# NANO_STM32F103_2.net
KiCad netlist of a schematic drawn in Altium Designer
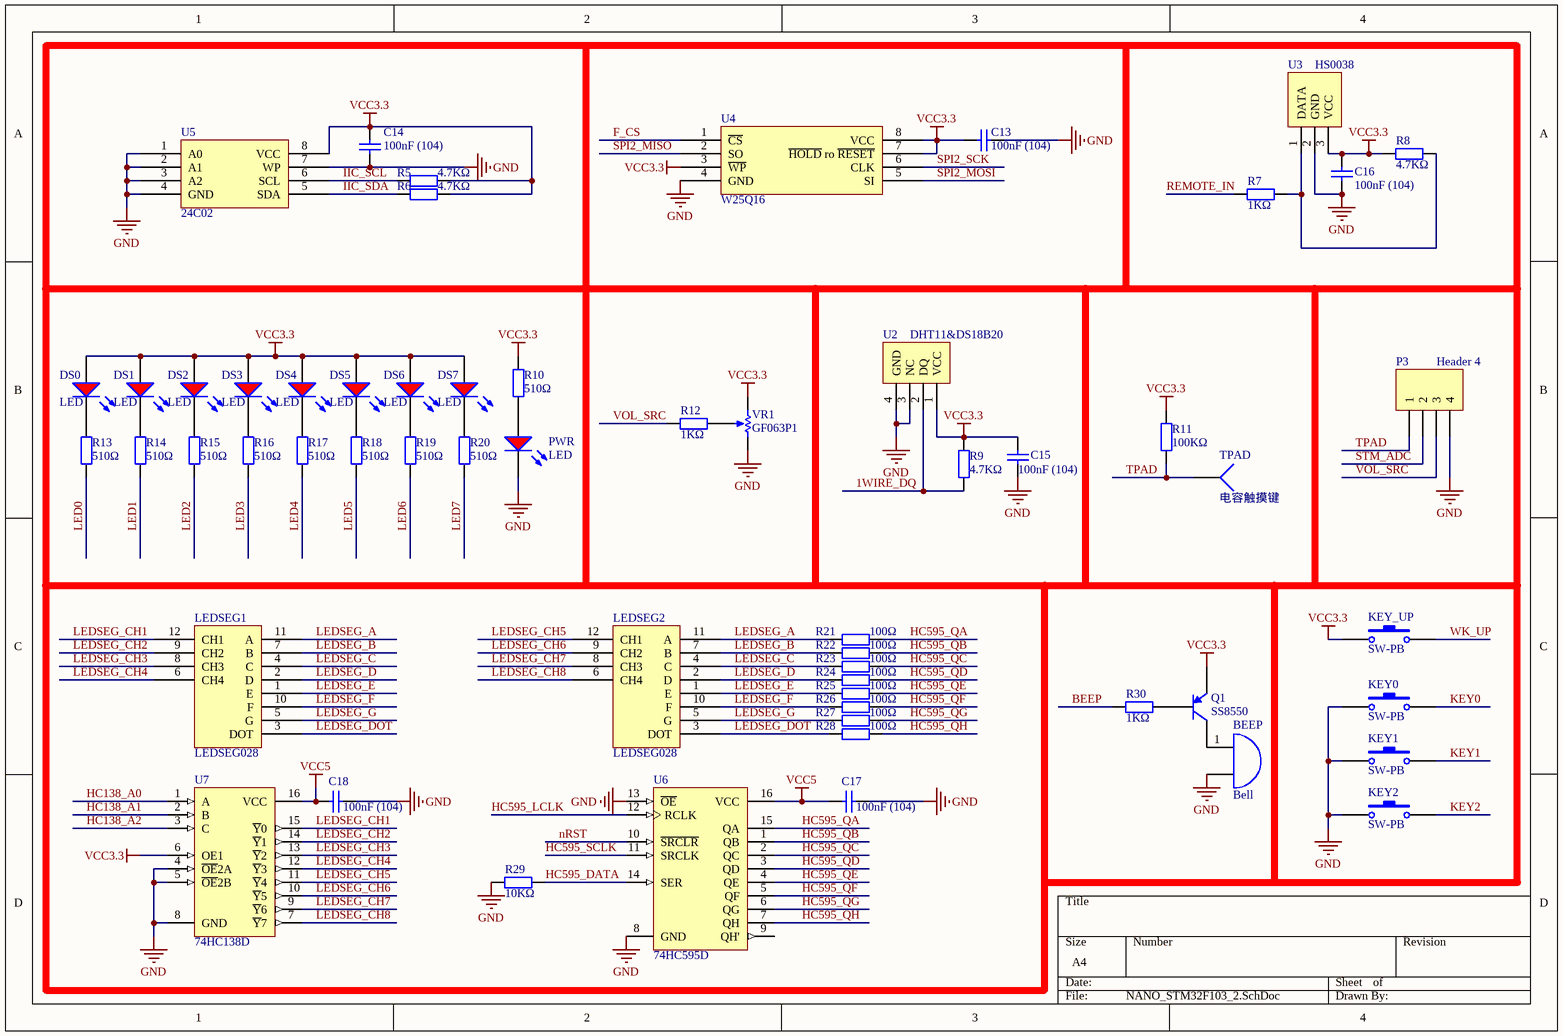
[diagram p0: NANO_STM32F103_2.SchDoc]

(export (version "E")
  (design (tool "Eeschema 10.0.6"))
  (components
    (comp (ref "BEEP")
      (value "Bell")
      (footprint "NANO_STM32F103:PIN2")
      (description "Electrical Bell")
      (fields (field (name "PUBLISHER") "Altium Limited"))
      (libsource (lib "Miscellaneous Devices") (part "Bell"))
    )
    (comp (ref "C13")
      (value "100nF (104)")
      (footprint "NANO_STM32F103:0603_C")
      (description "贴片电容")
      (libsource (lib "Miscellaneous Devices LC") (part "0603 100nF (104) 10% 50V"))
    )
    (comp (ref "C14")
      (value "100nF (104)")
      (footprint "NANO_STM32F103:0603_C")
      (description "贴片电容")
      (libsource (lib "Miscellaneous Devices LC") (part "0603 100nF (104) 10% 50V"))
    )
    (comp (ref "C15")
      (value "100nF (104)")
      (footprint "NANO_STM32F103:0603_C")
      (description "贴片电容")
      (libsource (lib "Miscellaneous Devices LC") (part "0603 100nF (104) 10% 50V"))
    )
    (comp (ref "C16")
      (value "100nF (104)")
      (footprint "NANO_STM32F103:0603_C")
      (description "贴片电容")
      (libsource (lib "Miscellaneous Devices LC") (part "0603 100nF (104) 10% 50V"))
    )
    (comp (ref "C17")
      (value "100nF (104)")
      (footprint "NANO_STM32F103:0603_C")
      (description "贴片电容")
      (libsource (lib "Miscellaneous Devices LC") (part "0603 100nF (104) 10% 50V"))
    )
    (comp (ref "C18")
      (value "100nF (104)")
      (footprint "NANO_STM32F103:0603_C")
      (description "贴片电容")
      (libsource (lib "Miscellaneous Devices LC") (part "0603 100nF (104) 10% 50V"))
    )
    (comp (ref "DS0")
      (value "LED")
      (footprint "NANO_STM32F103:0805_LED_S1")
      (description "发光二极管")
      (libsource (lib "Miscellaneous Devices LC") (part "0603 红灯"))
    )
    (comp (ref "DS1")
      (value "LED")
      (footprint "NANO_STM32F103:0805_LED_S1")
      (description "发光二极管")
      (libsource (lib "Miscellaneous Devices LC") (part "0603 红灯"))
    )
    (comp (ref "DS2")
      (value "LED")
      (footprint "NANO_STM32F103:0805_LED_S1")
      (description "发光二极管")
      (libsource (lib "Miscellaneous Devices LC") (part "0603 红灯"))
    )
    (comp (ref "DS3")
      (value "LED")
      (footprint "NANO_STM32F103:0805_LED_S1")
      (description "发光二极管")
      (libsource (lib "Miscellaneous Devices LC") (part "0603 红灯"))
    )
    (comp (ref "DS4")
      (value "LED")
      (footprint "NANO_STM32F103:0805_LED_S1")
      (description "发光二极管")
      (libsource (lib "Miscellaneous Devices LC") (part "0603 红灯"))
    )
    (comp (ref "DS5")
      (value "LED")
      (footprint "NANO_STM32F103:0805_LED_S1")
      (description "发光二极管")
      (libsource (lib "Miscellaneous Devices LC") (part "0603 红灯"))
    )
    (comp (ref "DS6")
      (value "LED")
      (footprint "NANO_STM32F103:0805_LED_S1")
      (description "发光二极管")
      (libsource (lib "Miscellaneous Devices LC") (part "0603 红灯"))
    )
    (comp (ref "DS7")
      (value "LED")
      (footprint "NANO_STM32F103:0805_LED_S1")
      (description "发光二极管")
      (libsource (lib "Miscellaneous Devices LC") (part "0603 红灯"))
    )
    (comp (ref "KEY0")
      (value "SW-PB")
      (footprint "NANO_STM32F103:SPST-2")
      (description "Switch")
      (fields (field (name "PUBLISHER") "Altium Limited"))
      (libsource (lib "Miscellaneous Devices") (part "SW-PB"))
    )
    (comp (ref "KEY1")
      (value "SW-PB")
      (footprint "NANO_STM32F103:SPST-2")
      (description "Switch")
      (fields (field (name "PUBLISHER") "Altium Limited"))
      (libsource (lib "Miscellaneous Devices") (part "SW-PB"))
    )
    (comp (ref "KEY2")
      (value "SW-PB")
      (footprint "NANO_STM32F103:SPST-2")
      (description "Switch")
      (fields (field (name "PUBLISHER") "Altium Limited"))
      (libsource (lib "Miscellaneous Devices") (part "SW-PB"))
    )
    (comp (ref "KEY_UP")
      (value "SW-PB")
      (footprint "NANO_STM32F103:SPST-2")
      (description "Switch")
      (fields (field (name "PUBLISHER") "Altium Limited"))
      (libsource (lib "Miscellaneous Devices") (part "SW-PB"))
    )
    (comp (ref "LEDSEG1")
      (value "LEDSEG028")
      (footprint "NANO_STM32F103:HDR1X12")
      (description "四位八段数码管_共阴极")
      (libsource (lib "NANO_STM32F103") (part "LEDSEG028"))
    )
    (comp (ref "LEDSEG2")
      (value "LEDSEG028")
      (footprint "NANO_STM32F103:HDR1X12")
      (description "四位八段数码管_共阴极")
      (libsource (lib "NANO_STM32F103") (part "LEDSEG028"))
    )
    (comp (ref "P3")
      (value "Header 4")
      (footprint "NANO_STM32F103:HDR1X4")
      (description "Header, 4-Pin")
      (fields (field (name "PUBLISHER") "Altium Limited"))
      (libsource (lib "Miscellaneous Connectors") (part "Header 4"))
    )
    (comp (ref "PWR")
      (value "LED")
      (footprint "NANO_STM32F103:0805_LED_S1")
      (description "发光二极管")
      (libsource (lib "Miscellaneous Devices LC") (part "0603 红灯"))
    )
    (comp (ref "Q1")
      (value "SS8550")
      (footprint "NANO_STM32F103:SOT-23(SOT-23-3)")
      (description "PNP三极管")
      (libsource (lib "Miscellaneous Devices LC") (part "SOT-23 SS8550 Y2"))
    )
    (comp (ref "R5")
      (value "4.7KΩ")
      (footprint "NANO_STM32F103:0603_R")
      (description "贴片电阻")
      (libsource (lib "Miscellaneous Devices LC") (part "0603 4.7KΩ (4701) 1%"))
    )
    (comp (ref "R6")
      (value "4.7KΩ")
      (footprint "NANO_STM32F103:0603_R")
      (description "贴片电阻")
      (libsource (lib "Miscellaneous Devices LC") (part "0603 4.7KΩ (4701) 1%"))
    )
    (comp (ref "R7")
      (value "1KΩ")
      (footprint "NANO_STM32F103:0603_R")
      (description "贴片电阻")
      (libsource (lib "Miscellaneous Devices LC") (part "0603 1KΩ (1001) 1%"))
    )
    (comp (ref "R8")
      (value "4.7KΩ")
      (footprint "NANO_STM32F103:0603_R")
      (description "贴片电阻")
      (libsource (lib "Miscellaneous Devices LC") (part "0603 4.7KΩ (4701) 1%"))
    )
    (comp (ref "R9")
      (value "4.7KΩ")
      (footprint "NANO_STM32F103:0603_R")
      (description "贴片电阻")
      (libsource (lib "") (part "0603 4.7KΩ (4701) 1%_1"))
    )
    (comp (ref "R10")
      (value "510Ω")
      (footprint "NANO_STM32F103:0603_R")
      (description "贴片电阻")
      (libsource (lib "Miscellaneous Devices LC") (part "0603 510Ω (5100) 1%"))
    )
    (comp (ref "R11")
      (value "100KΩ")
      (footprint "NANO_STM32F103:0603_R")
      (description "贴片电阻")
      (libsource (lib "Miscellaneous Devices LC") (part "0603 100KΩ (1003) 1%"))
    )
    (comp (ref "R12")
      (value "1KΩ")
      (footprint "NANO_STM32F103:0603_R")
      (description "贴片电阻")
      (libsource (lib "Miscellaneous Devices LC") (part "0603 1KΩ (1001) 1%"))
    )
    (comp (ref "R13")
      (value "510Ω")
      (footprint "NANO_STM32F103:0603_R")
      (description "贴片电阻")
      (libsource (lib "Miscellaneous Devices LC") (part "0603 510Ω (5100) 1%"))
    )
    (comp (ref "R14")
      (value "510Ω")
      (footprint "NANO_STM32F103:0603_R")
      (description "贴片电阻")
      (libsource (lib "Miscellaneous Devices LC") (part "0603 510Ω (5100) 1%"))
    )
    (comp (ref "R15")
      (value "510Ω")
      (footprint "NANO_STM32F103:0603_R")
      (description "贴片电阻")
      (libsource (lib "Miscellaneous Devices LC") (part "0603 510Ω (5100) 1%"))
    )
    (comp (ref "R16")
      (value "510Ω")
      (footprint "NANO_STM32F103:0603_R")
      (description "贴片电阻")
      (libsource (lib "Miscellaneous Devices LC") (part "0603 510Ω (5100) 1%"))
    )
    (comp (ref "R17")
      (value "510Ω")
      (footprint "NANO_STM32F103:0603_R")
      (description "贴片电阻")
      (libsource (lib "Miscellaneous Devices LC") (part "0603 510Ω (5100) 1%"))
    )
    (comp (ref "R18")
      (value "510Ω")
      (footprint "NANO_STM32F103:0603_R")
      (description "贴片电阻")
      (libsource (lib "Miscellaneous Devices LC") (part "0603 510Ω (5100) 1%"))
    )
    (comp (ref "R19")
      (value "510Ω")
      (footprint "NANO_STM32F103:0603_R")
      (description "贴片电阻")
      (libsource (lib "Miscellaneous Devices LC") (part "0603 510Ω (5100) 1%"))
    )
    (comp (ref "R20")
      (value "510Ω")
      (footprint "NANO_STM32F103:0603_R")
      (description "贴片电阻")
      (libsource (lib "Miscellaneous Devices LC") (part "0603 510Ω (5100) 1%"))
    )
    (comp (ref "R21")
      (value "100Ω")
      (footprint "NANO_STM32F103:0603_R")
      (description "贴片电阻")
      (libsource (lib "Miscellaneous Devices LC") (part "0603 100Ω (1000) 1%"))
    )
    (comp (ref "R22")
      (value "100Ω")
      (footprint "NANO_STM32F103:0603_R")
      (description "贴片电阻")
      (libsource (lib "Miscellaneous Devices LC") (part "0603 100Ω (1000) 1%"))
    )
    (comp (ref "R23")
      (value "100Ω")
      (footprint "NANO_STM32F103:0603_R")
      (description "贴片电阻")
      (libsource (lib "Miscellaneous Devices LC") (part "0603 100Ω (1000) 1%"))
    )
    (comp (ref "R24")
      (value "100Ω")
      (footprint "NANO_STM32F103:0603_R")
      (description "贴片电阻")
      (libsource (lib "Miscellaneous Devices LC") (part "0603 100Ω (1000) 1%"))
    )
    (comp (ref "R25")
      (value "100Ω")
      (footprint "NANO_STM32F103:0603_R")
      (description "贴片电阻")
      (libsource (lib "Miscellaneous Devices LC") (part "0603 100Ω (1000) 1%"))
    )
    (comp (ref "R26")
      (value "100Ω")
      (footprint "NANO_STM32F103:0603_R")
      (description "贴片电阻")
      (libsource (lib "Miscellaneous Devices LC") (part "0603 100Ω (1000) 1%"))
    )
    (comp (ref "R27")
      (value "100Ω")
      (footprint "NANO_STM32F103:0603_R")
      (description "贴片电阻")
      (libsource (lib "Miscellaneous Devices LC") (part "0603 100Ω (1000) 1%"))
    )
    (comp (ref "R28")
      (value "100Ω")
      (footprint "NANO_STM32F103:0603_R")
      (description "贴片电阻")
      (libsource (lib "Miscellaneous Devices LC") (part "0603 100Ω (1000) 1%"))
    )
    (comp (ref "R29")
      (value "10KΩ")
      (footprint "NANO_STM32F103:0603_R")
      (description "贴片电阻")
      (libsource (lib "Miscellaneous Devices LC") (part "0603 10KΩ (1002) 1%"))
    )
    (comp (ref "R30")
      (value "1KΩ")
      (footprint "NANO_STM32F103:0603_R")
      (description "贴片电阻")
      (libsource (lib "Miscellaneous Devices LC") (part "0603 1KΩ (1001) 1%"))
    )
    (comp (ref "TPAD")
      (value "电容触摸键")
      (footprint "NANO_STM32F103:TPAD")
      (fields (field (name "PUBLISHER") "Altium Limited"))
      (libsource (lib "Miscellaneous Connectors") (part "Socket"))
    )
    (comp (ref "U2")
      (value "DHT11&DS18B20")
      (footprint "DHT11&DS18B20")
      (description "DHT11或DS18B20_2.54mm")
      (libsource (lib "NANO_STM32F103_2") (part "DHT11&DS18B20"))
    )
    (comp (ref "U3")
      (value "HS0038")
      (footprint "NANO_STM32F103:HS0038")
      (description "HS0038_2.54mm")
      (libsource (lib "NANO_STM32F103_2") (part "HS0038"))
    )
    (comp (ref "U4")
      (value "W25Q16")
      (footprint "NANO_STM32F103:SOIC-8_208mil")
      (description "Flash ROM")
      (libsource (lib "Miscellaneous Devices LC") (part "W25Q128FVSIG_[C35101]"))
    )
    (comp (ref "U5")
      (value "24C02")
      (footprint "NANO_STM32F103:SOIC-8_150mil")
      (libsource (lib "Miscellaneous Devices LC") (part "CAN/TJA1050T/CM_[C6952]"))
    )
    (comp (ref "U6")
      (value "74HC595D")
      (footprint "NANO_STM32F103:SOIC-16_150mil")
      (description "74系列逻辑芯片")
      (libsource (lib "Miscellaneous Devices LC") (part "74HC595D_[C5947]"))
    )
    (comp (ref "U7")
      (value "74HC138D")
      (footprint "NANO_STM32F103:SOIC-16_150mil")
      (description "74系列逻辑芯片")
      (libsource (lib "Miscellaneous Devices LC") (part "74HC138D_[C5602]"))
    )
    (comp (ref "VR1")
      (value "GF063P1")
      (footprint "NANO_STM32F103:VR5")
      (description "滑动变阻器")
      (fields (field (name "PUBLISHER") "Altium Limited"))
      (libsource (lib "Miscellaneous Devices") (part "RPot"))
    )
  )
  (nets
    (net (code "1") (name "/1WIRE_DQ") (class "Default")
      (node (ref "R9") (pin "1") (pinfunction "1_1") (pintype "passive"))
      (node (ref "U2") (pin "2") (pinfunction "DQ_2") (pintype "passive"))
    )
    (net (code "2") (name "/BEEP") (class "Default")
      (node (ref "R30") (pin "1") (pinfunction "1_1") (pintype "passive"))
    )
    (net (code "3") (name "/F_CS") (class "Default")
      (node (ref "U4") (pin "1") (pinfunction "~{CS}_1") (pintype "passive"))
    )
    (net (code "4") (name "/HC138_A0") (class "Default")
      (node (ref "U7") (pin "1") (pinfunction "A_1") (pintype "input"))
    )
    (net (code "5") (name "/HC138_A1") (class "Default")
      (node (ref "U7") (pin "2") (pinfunction "B_2") (pintype "input"))
    )
    (net (code "6") (name "/HC138_A2") (class "Default")
      (node (ref "U7") (pin "3") (pinfunction "C_3") (pintype "input"))
    )
    (net (code "7") (name "/HC595_DATA") (class "Default")
      (node (ref "R29") (pin "2") (pinfunction "2_2") (pintype "passive"))
      (node (ref "U6") (pin "14") (pinfunction "SER_14") (pintype "input"))
    )
    (net (code "8") (name "/HC595_LCLK") (class "Default")
      (node (ref "U6") (pin "12") (pinfunction "RCLK_12") (pintype "input"))
    )
    (net (code "9") (name "/HC595_QA") (class "Default")
      (node (ref "R21") (pin "2") (pinfunction "2_2") (pintype "passive"))
      (node (ref "U6") (pin "15") (pinfunction "QA_15") (pintype "tri_state"))
    )
    (net (code "10") (name "/HC595_QB") (class "Default")
      (node (ref "R22") (pin "2") (pinfunction "2_2") (pintype "passive"))
      (node (ref "U6") (pin "1") (pinfunction "QB_1") (pintype "tri_state"))
    )
    (net (code "11") (name "/HC595_QC") (class "Default")
      (node (ref "R23") (pin "2") (pinfunction "2_2") (pintype "passive"))
      (node (ref "U6") (pin "2") (pinfunction "QC_2") (pintype "tri_state"))
    )
    (net (code "12") (name "/HC595_QD") (class "Default")
      (node (ref "R24") (pin "2") (pinfunction "2_2") (pintype "passive"))
      (node (ref "U6") (pin "3") (pinfunction "QD_3") (pintype "tri_state"))
    )
    (net (code "13") (name "/HC595_QE") (class "Default")
      (node (ref "R25") (pin "2") (pinfunction "2_2") (pintype "passive"))
      (node (ref "U6") (pin "4") (pinfunction "QE_4") (pintype "tri_state"))
    )
    (net (code "14") (name "/HC595_QF") (class "Default")
      (node (ref "R26") (pin "2") (pinfunction "2_2") (pintype "passive"))
      (node (ref "U6") (pin "5") (pinfunction "QF_5") (pintype "tri_state"))
    )
    (net (code "15") (name "/HC595_QG") (class "Default")
      (node (ref "R27") (pin "2") (pinfunction "2_2") (pintype "passive"))
      (node (ref "U6") (pin "6") (pinfunction "QG_6") (pintype "tri_state"))
    )
    (net (code "16") (name "/HC595_QH") (class "Default")
      (node (ref "R28") (pin "2") (pinfunction "2_2") (pintype "passive"))
      (node (ref "U6") (pin "7") (pinfunction "QH_7") (pintype "tri_state"))
    )
    (net (code "17") (name "/HC595_SCLK") (class "Default")
      (node (ref "U6") (pin "11") (pinfunction "SRCLK_11") (pintype "input"))
    )
    (net (code "18") (name "/IIC_SCL") (class "Default")
      (node (ref "R5") (pin "1") (pinfunction "1_1") (pintype "passive"))
      (node (ref "U5") (pin "6") (pinfunction "SCL_6") (pintype "passive"))
    )
    (net (code "19") (name "/IIC_SDA") (class "Default")
      (node (ref "R6") (pin "1") (pinfunction "1_1") (pintype "passive"))
      (node (ref "U5") (pin "5") (pinfunction "SDA_5") (pintype "passive"))
    )
    (net (code "20") (name "/KEY0") (class "Default")
      (node (ref "KEY0") (pin "2") (pinfunction "2_2") (pintype "passive"))
    )
    (net (code "21") (name "/KEY1") (class "Default")
      (node (ref "KEY1") (pin "2") (pinfunction "2_2") (pintype "passive"))
    )
    (net (code "22") (name "/KEY2") (class "Default")
      (node (ref "KEY2") (pin "2") (pinfunction "2_2") (pintype "passive"))
    )
    (net (code "23") (name "/LED0") (class "Default")
      (node (ref "R13") (pin "2") (pinfunction "2_2") (pintype "passive"))
    )
    (net (code "24") (name "/LED1") (class "Default")
      (node (ref "R14") (pin "2") (pinfunction "2_2") (pintype "passive"))
    )
    (net (code "25") (name "/LED2") (class "Default")
      (node (ref "R15") (pin "2") (pinfunction "2_2") (pintype "passive"))
    )
    (net (code "26") (name "/LED3") (class "Default")
      (node (ref "R16") (pin "2") (pinfunction "2_2") (pintype "passive"))
    )
    (net (code "27") (name "/LED4") (class "Default")
      (node (ref "R17") (pin "2") (pinfunction "2_2") (pintype "passive"))
    )
    (net (code "28") (name "/LED5") (class "Default")
      (node (ref "R18") (pin "2") (pinfunction "2_2") (pintype "passive"))
    )
    (net (code "29") (name "/LED6") (class "Default")
      (node (ref "R19") (pin "2") (pinfunction "2_2") (pintype "passive"))
    )
    (net (code "30") (name "/LED7") (class "Default")
      (node (ref "R20") (pin "2") (pinfunction "2_2") (pintype "passive"))
    )
    (net (code "31") (name "/LEDSEG_A") (class "Default")
      (node (ref "LEDSEG1") (pin "11") (pinfunction "A_11") (pintype "passive"))
      (node (ref "LEDSEG2") (pin "11") (pinfunction "A_11") (pintype "passive"))
      (node (ref "R21") (pin "1") (pinfunction "1_1") (pintype "passive"))
    )
    (net (code "32") (name "/LEDSEG_B") (class "Default")
      (node (ref "LEDSEG1") (pin "7") (pinfunction "B_7") (pintype "passive"))
      (node (ref "LEDSEG2") (pin "7") (pinfunction "B_7") (pintype "passive"))
      (node (ref "R22") (pin "1") (pinfunction "1_1") (pintype "passive"))
    )
    (net (code "33") (name "/LEDSEG_C") (class "Default")
      (node (ref "LEDSEG1") (pin "4") (pinfunction "C_4") (pintype "passive"))
      (node (ref "LEDSEG2") (pin "4") (pinfunction "C_4") (pintype "passive"))
      (node (ref "R23") (pin "1") (pinfunction "1_1") (pintype "passive"))
    )
    (net (code "34") (name "/LEDSEG_CH1") (class "Default")
      (node (ref "LEDSEG1") (pin "12") (pinfunction "CH1_12") (pintype "passive"))
      (node (ref "U7") (pin "15") (pinfunction "~{Y}0_15") (pintype "output"))
    )
    (net (code "35") (name "/LEDSEG_CH2") (class "Default")
      (node (ref "LEDSEG1") (pin "9") (pinfunction "CH2_9") (pintype "passive"))
      (node (ref "U7") (pin "14") (pinfunction "~{Y}1_14") (pintype "output"))
    )
    (net (code "36") (name "/LEDSEG_CH3") (class "Default")
      (node (ref "LEDSEG1") (pin "8") (pinfunction "CH3_8") (pintype "passive"))
      (node (ref "U7") (pin "13") (pinfunction "~{Y}2_13") (pintype "output"))
    )
    (net (code "37") (name "/LEDSEG_CH4") (class "Default")
      (node (ref "LEDSEG1") (pin "6") (pinfunction "CH4_6") (pintype "passive"))
      (node (ref "U7") (pin "12") (pinfunction "~{Y}3_12") (pintype "output"))
    )
    (net (code "38") (name "/LEDSEG_CH5") (class "Default")
      (node (ref "LEDSEG2") (pin "12") (pinfunction "CH1_12") (pintype "passive"))
      (node (ref "U7") (pin "11") (pinfunction "~{Y}4_11") (pintype "output"))
    )
    (net (code "39") (name "/LEDSEG_CH6") (class "Default")
      (node (ref "LEDSEG2") (pin "9") (pinfunction "CH2_9") (pintype "passive"))
      (node (ref "U7") (pin "10") (pinfunction "~{Y}5_10") (pintype "output"))
    )
    (net (code "40") (name "/LEDSEG_CH7") (class "Default")
      (node (ref "LEDSEG2") (pin "8") (pinfunction "CH3_8") (pintype "passive"))
      (node (ref "U7") (pin "9") (pinfunction "~{Y}6_9") (pintype "output"))
    )
    (net (code "41") (name "/LEDSEG_CH8") (class "Default")
      (node (ref "LEDSEG2") (pin "6") (pinfunction "CH4_6") (pintype "passive"))
      (node (ref "U7") (pin "7") (pinfunction "~{Y}7_7") (pintype "output"))
    )
    (net (code "42") (name "/LEDSEG_D") (class "Default")
      (node (ref "LEDSEG1") (pin "2") (pinfunction "D_2") (pintype "passive"))
      (node (ref "LEDSEG2") (pin "2") (pinfunction "D_2") (pintype "passive"))
      (node (ref "R24") (pin "1") (pinfunction "1_1") (pintype "passive"))
    )
    (net (code "43") (name "/LEDSEG_DOT") (class "Default")
      (node (ref "LEDSEG1") (pin "3") (pinfunction "DOT_3") (pintype "passive"))
      (node (ref "LEDSEG2") (pin "3") (pinfunction "DOT_3") (pintype "passive"))
      (node (ref "R28") (pin "1") (pinfunction "1_1") (pintype "passive"))
    )
    (net (code "44") (name "/LEDSEG_E") (class "Default")
      (node (ref "LEDSEG1") (pin "1") (pinfunction "E_1") (pintype "passive"))
      (node (ref "LEDSEG2") (pin "1") (pinfunction "E_1") (pintype "passive"))
      (node (ref "R25") (pin "1") (pinfunction "1_1") (pintype "passive"))
    )
    (net (code "45") (name "/LEDSEG_F") (class "Default")
      (node (ref "LEDSEG1") (pin "10") (pinfunction "F_10") (pintype "passive"))
      (node (ref "LEDSEG2") (pin "10") (pinfunction "F_10") (pintype "passive"))
      (node (ref "R26") (pin "1") (pinfunction "1_1") (pintype "passive"))
    )
    (net (code "46") (name "/LEDSEG_G") (class "Default")
      (node (ref "LEDSEG1") (pin "5") (pinfunction "G_5") (pintype "passive"))
      (node (ref "LEDSEG2") (pin "5") (pinfunction "G_5") (pintype "passive"))
      (node (ref "R27") (pin "1") (pinfunction "1_1") (pintype "passive"))
    )
    (net (code "47") (name "/REMOTE_IN") (class "Default")
      (node (ref "R7") (pin "1") (pinfunction "1_1") (pintype "passive"))
    )
    (net (code "48") (name "/SPI2_MISO") (class "Default")
      (node (ref "U4") (pin "2") (pinfunction "SO_2") (pintype "passive"))
    )
    (net (code "49") (name "/SPI2_MOSI") (class "Default")
      (node (ref "U4") (pin "5") (pinfunction "SI_5") (pintype "passive"))
    )
    (net (code "50") (name "/SPI2_SCK") (class "Default")
      (node (ref "U4") (pin "6") (pinfunction "CLK_6") (pintype "passive"))
    )
    (net (code "51") (name "/STM_ADC") (class "Default")
      (node (ref "P3") (pin "2") (pinfunction "2_2") (pintype "passive"))
    )
    (net (code "52") (name "/TPAD") (class "Default")
      (node (ref "P3") (pin "1") (pinfunction "1_1") (pintype "passive"))
      (node (ref "R11") (pin "2") (pinfunction "2_2") (pintype "passive"))
      (node (ref "TPAD") (pin "1") (pinfunction "1_1") (pintype "passive"))
    )
    (net (code "53") (name "/VOL_SRC") (class "Default")
      (node (ref "P3") (pin "3") (pinfunction "3_3") (pintype "passive"))
      (node (ref "R12") (pin "1") (pinfunction "1_1") (pintype "passive"))
    )
    (net (code "54") (name "/WK_UP") (class "Default")
      (node (ref "KEY_UP") (pin "2") (pinfunction "2_2") (pintype "passive"))
    )
    (net (code "55") (name "/nRST") (class "Default")
      (node (ref "U6") (pin "10") (pinfunction "~{SRCLR}_10") (pintype "input"))
    )
    (net (code "56") (name "GND") (class "Default")
      (node (ref "BEEP") (pin "2") (pinfunction "B_2") (pintype "passive"))
      (node (ref "C13") (pin "2") (pinfunction "2_2") (pintype "passive"))
      (node (ref "C14") (pin "1") (pinfunction "1_1") (pintype "passive"))
      (node (ref "C15") (pin "2") (pinfunction "2_2") (pintype "passive"))
      (node (ref "C16") (pin "2") (pinfunction "2_2") (pintype "passive"))
      (node (ref "C17") (pin "2") (pinfunction "2_2") (pintype "passive"))
      (node (ref "C18") (pin "2") (pinfunction "2_2") (pintype "passive"))
      (node (ref "KEY0") (pin "1") (pinfunction "1_1") (pintype "passive"))
      (node (ref "KEY1") (pin "1") (pinfunction "1_1") (pintype "passive"))
      (node (ref "KEY2") (pin "1") (pinfunction "1_1") (pintype "passive"))
      (node (ref "P3") (pin "4") (pinfunction "4_4") (pintype "passive"))
      (node (ref "PWR") (pin "K") (pinfunction "K_K") (pintype "passive"))
      (node (ref "R29") (pin "1") (pinfunction "1_1") (pintype "passive"))
      (node (ref "U2") (pin "3") (pinfunction "NC_3") (pintype "passive"))
      (node (ref "U2") (pin "4") (pinfunction "GND_4") (pintype "passive"))
      (node (ref "U3") (pin "2") (pinfunction "GND_2") (pintype "passive"))
      (node (ref "U4") (pin "4") (pinfunction "GND_4") (pintype "passive"))
      (node (ref "U5") (pin "1") (pinfunction "A0_1") (pintype "passive"))
      (node (ref "U5") (pin "2") (pinfunction "A1_2") (pintype "passive"))
      (node (ref "U5") (pin "3") (pinfunction "A2_3") (pintype "passive"))
      (node (ref "U5") (pin "4") (pinfunction "GND_4") (pintype "passive"))
      (node (ref "U5") (pin "7") (pinfunction "WP_7") (pintype "passive"))
      (node (ref "U6") (pin "13") (pinfunction "~{OE}_13") (pintype "input"))
      (node (ref "U6") (pin "8") (pinfunction "GND_8") (pintype "power_in"))
      (node (ref "U7") (pin "4") (pinfunction "~{OE}2A_4") (pintype "input"))
      (node (ref "U7") (pin "5") (pinfunction "~{OE}2B_5") (pintype "input"))
      (node (ref "U7") (pin "8") (pinfunction "GND_8") (pintype "power_in"))
      (node (ref "VR1") (pin "2") (pinfunction "BOT_2") (pintype "passive"))
    )
    (net (code "57") (name "Net-(BEEP-A)") (class "Default")
      (node (ref "BEEP") (pin "1") (pinfunction "A_1") (pintype "passive"))
      (node (ref "Q1") (pin "3") (pinfunction "C_3") (pintype "passive"))
    )
    (net (code "58") (name "Net-(DS0-PadK)") (class "Default")
      (node (ref "DS0") (pin "K") (pinfunction "K_K") (pintype "passive"))
      (node (ref "R13") (pin "1") (pinfunction "1_1") (pintype "passive"))
    )
    (net (code "59") (name "Net-(DS1-PadK)") (class "Default")
      (node (ref "DS1") (pin "K") (pinfunction "K_K") (pintype "passive"))
      (node (ref "R14") (pin "1") (pinfunction "1_1") (pintype "passive"))
    )
    (net (code "60") (name "Net-(DS2-PadK)") (class "Default")
      (node (ref "DS2") (pin "K") (pinfunction "K_K") (pintype "passive"))
      (node (ref "R15") (pin "1") (pinfunction "1_1") (pintype "passive"))
    )
    (net (code "61") (name "Net-(DS3-PadK)") (class "Default")
      (node (ref "DS3") (pin "K") (pinfunction "K_K") (pintype "passive"))
      (node (ref "R16") (pin "1") (pinfunction "1_1") (pintype "passive"))
    )
    (net (code "62") (name "Net-(DS4-PadK)") (class "Default")
      (node (ref "DS4") (pin "K") (pinfunction "K_K") (pintype "passive"))
      (node (ref "R17") (pin "1") (pinfunction "1_1") (pintype "passive"))
    )
    (net (code "63") (name "Net-(DS5-PadK)") (class "Default")
      (node (ref "DS5") (pin "K") (pinfunction "K_K") (pintype "passive"))
      (node (ref "R18") (pin "1") (pinfunction "1_1") (pintype "passive"))
    )
    (net (code "64") (name "Net-(DS6-PadK)") (class "Default")
      (node (ref "DS6") (pin "K") (pinfunction "K_K") (pintype "passive"))
      (node (ref "R19") (pin "1") (pinfunction "1_1") (pintype "passive"))
    )
    (net (code "65") (name "Net-(DS7-PadK)") (class "Default")
      (node (ref "DS7") (pin "K") (pinfunction "K_K") (pintype "passive"))
      (node (ref "R20") (pin "1") (pinfunction "1_1") (pintype "passive"))
    )
    (net (code "66") (name "Net-(PWR-PadA)") (class "Default")
      (node (ref "PWR") (pin "A") (pinfunction "A_A") (pintype "passive"))
      (node (ref "R10") (pin "2") (pinfunction "2_2") (pintype "passive"))
    )
    (net (code "67") (name "Net-(Q1-B)") (class "Default")
      (node (ref "Q1") (pin "1") (pinfunction "B_1") (pintype "passive"))
      (node (ref "R30") (pin "2") (pinfunction "2_2") (pintype "passive"))
    )
    (net (code "68") (name "Net-(U3-DATA)") (class "Default")
      (node (ref "R7") (pin "2") (pinfunction "2_2") (pintype "passive"))
      (node (ref "R8") (pin "2") (pinfunction "2_2") (pintype "passive"))
      (node (ref "U3") (pin "1") (pinfunction "DATA_1") (pintype "passive"))
    )
    (net (code "69") (name "Net-(VR1-TAP)") (class "Default")
      (node (ref "R12") (pin "2") (pinfunction "2_2") (pintype "passive"))
      (node (ref "VR1") (pin "3") (pinfunction "TAP_3") (pintype "passive"))
    )
    (net (code "70") (name "VCC3.3") (class "Default")
      (node (ref "C13") (pin "1") (pinfunction "1_1") (pintype "passive"))
      (node (ref "C14") (pin "2") (pinfunction "2_2") (pintype "passive"))
      (node (ref "C15") (pin "1") (pinfunction "1_1") (pintype "passive"))
      (node (ref "C16") (pin "1") (pinfunction "1_1") (pintype "passive"))
      (node (ref "DS0") (pin "A") (pinfunction "A_A") (pintype "passive"))
      (node (ref "DS1") (pin "A") (pinfunction "A_A") (pintype "passive"))
      (node (ref "DS2") (pin "A") (pinfunction "A_A") (pintype "passive"))
      (node (ref "DS3") (pin "A") (pinfunction "A_A") (pintype "passive"))
      (node (ref "DS4") (pin "A") (pinfunction "A_A") (pintype "passive"))
      (node (ref "DS5") (pin "A") (pinfunction "A_A") (pintype "passive"))
      (node (ref "DS6") (pin "A") (pinfunction "A_A") (pintype "passive"))
      (node (ref "DS7") (pin "A") (pinfunction "A_A") (pintype "passive"))
      (node (ref "KEY_UP") (pin "1") (pinfunction "1_1") (pintype "passive"))
      (node (ref "Q1") (pin "2") (pinfunction "E_2") (pintype "passive"))
      (node (ref "R10") (pin "1") (pinfunction "1_1") (pintype "passive"))
      (node (ref "R11") (pin "1") (pinfunction "1_1") (pintype "passive"))
      (node (ref "R5") (pin "2") (pinfunction "2_2") (pintype "passive"))
      (node (ref "R6") (pin "2") (pinfunction "2_2") (pintype "passive"))
      (node (ref "R8") (pin "1") (pinfunction "1_1") (pintype "passive"))
      (node (ref "R9") (pin "2") (pinfunction "2_2") (pintype "passive"))
      (node (ref "U2") (pin "1") (pinfunction "VCC_1") (pintype "passive"))
      (node (ref "U3") (pin "3") (pinfunction "VCC_3") (pintype "passive"))
      (node (ref "U4") (pin "3") (pinfunction "~{WP}_3") (pintype "passive"))
      (node (ref "U4") (pin "7") (pinfunction "~{HOLD}_ro_~{RESET}_7") (pintype "passive"))
      (node (ref "U4") (pin "8") (pinfunction "VCC_8") (pintype "passive"))
      (node (ref "U5") (pin "8") (pinfunction "VCC_8") (pintype "passive"))
      (node (ref "U7") (pin "6") (pinfunction "OE1_6") (pintype "input"))
      (node (ref "VR1") (pin "1") (pinfunction "TOP_1") (pintype "passive"))
    )
    (net (code "71") (name "VCC5") (class "Default")
      (node (ref "C17") (pin "1") (pinfunction "1_1") (pintype "passive"))
      (node (ref "C18") (pin "1") (pinfunction "1_1") (pintype "passive"))
      (node (ref "U6") (pin "16") (pinfunction "VCC_16") (pintype "power_in"))
      (node (ref "U7") (pin "16") (pinfunction "VCC_16") (pintype "power_in"))
    )
    (net (code "72") (name "unconnected-(U6-QH'-Pad9)") (class "Default")
      (node (ref "U6") (pin "9") (pinfunction "QH'_9") (pintype "output"))
    )
  )
)
